# LTC4418_Schematic.net
KiCad netlist of a schematic drawn in EAGLE
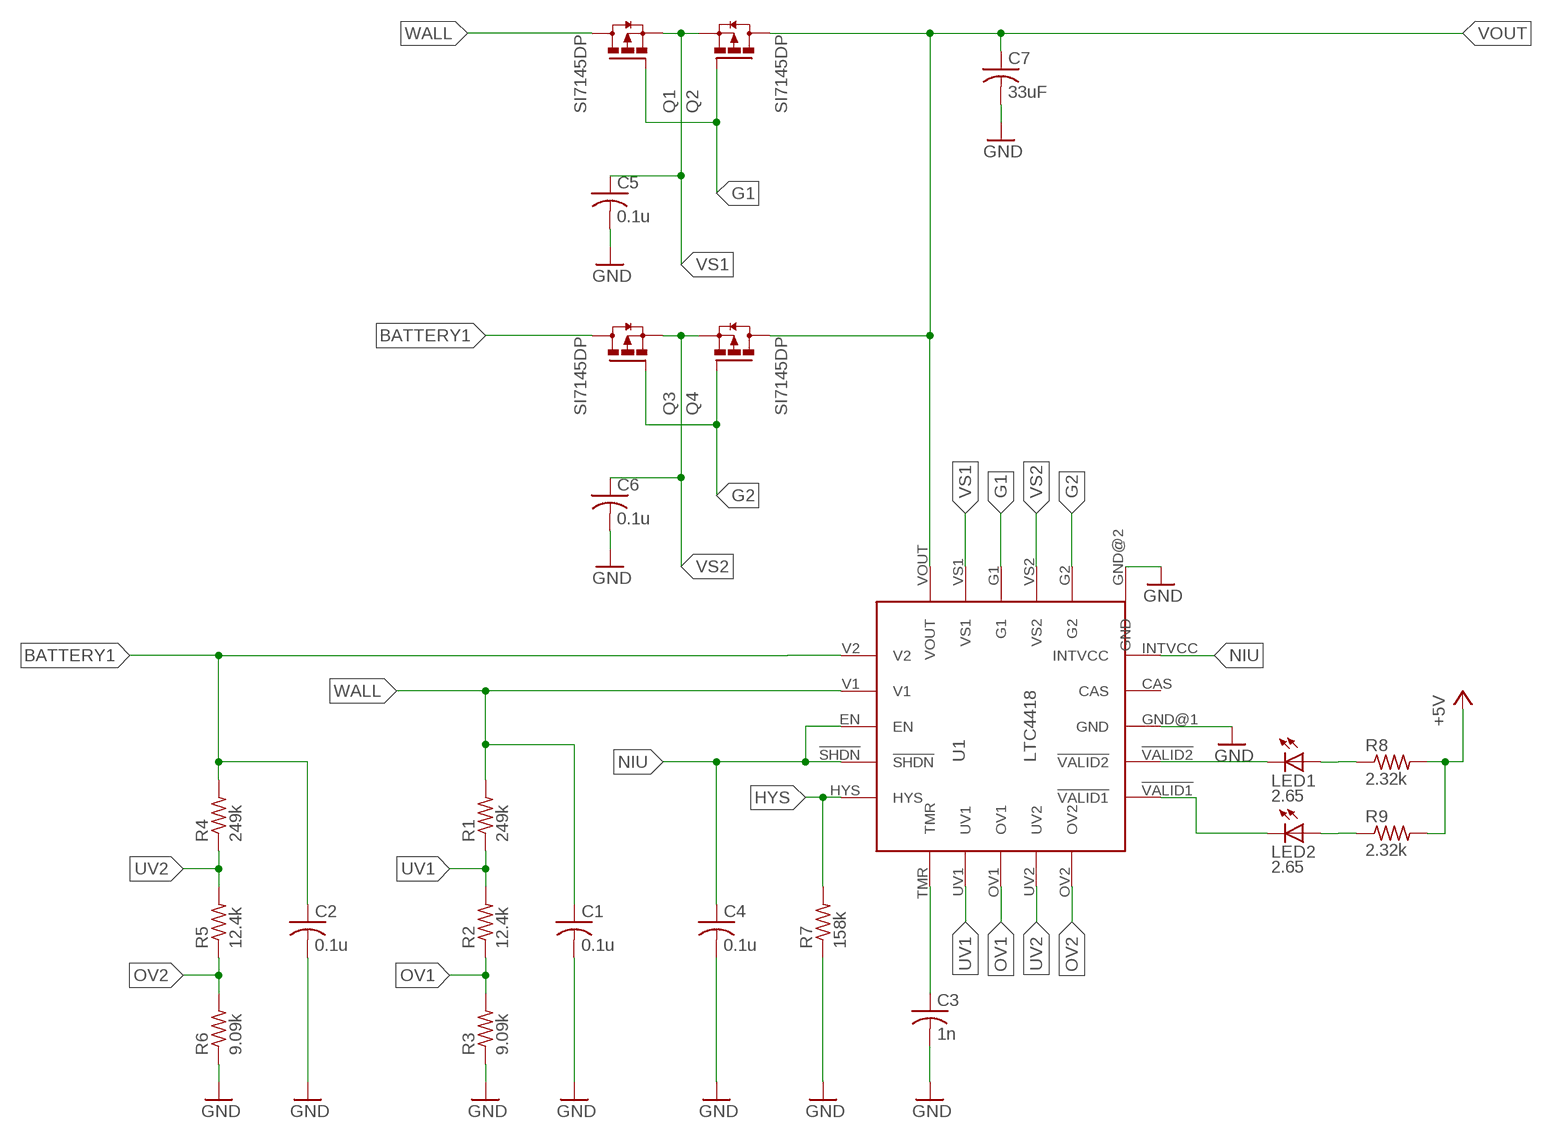
[diagram p0: schematic, sheet 1]

(export (version "E")
  (design (tool "Eeschema 10.0.6"))
  (components
    (comp (ref "C1")
      (value "0.1u")
      (footprint "eagle-import:C1206")
      (libsource (lib "eagle-import") (part "C-USC1206"))
    )
    (comp (ref "C2")
      (value "0.1u")
      (footprint "eagle-import:C1206")
      (libsource (lib "eagle-import") (part "C-USC1206"))
    )
    (comp (ref "C3")
      (value "1n")
      (footprint "eagle-import:C1206")
      (libsource (lib "eagle-import") (part "C-USC1206"))
    )
    (comp (ref "C4")
      (value "0.1u")
      (footprint "eagle-import:C1206")
      (libsource (lib "eagle-import") (part "C-USC1206"))
    )
    (comp (ref "C5")
      (value "0.1u")
      (footprint "eagle-import:C1206")
      (libsource (lib "eagle-import") (part "C-USC1206"))
    )
    (comp (ref "C6")
      (value "0.1u")
      (footprint "eagle-import:C1206")
      (libsource (lib "eagle-import") (part "C-USC1206"))
    )
    (comp (ref "C7")
      (value "33uF")
      (footprint "eagle-import:C1206")
      (libsource (lib "eagle-import") (part "C-USC1206"))
    )
    (comp (ref "LED1")
      (value "2.65")
      (footprint "eagle-import:SML0805")
      (libsource (lib "eagle-import") (part "LEDSML0805"))
    )
    (comp (ref "LED2")
      (value "2.65")
      (footprint "eagle-import:SML0805")
      (libsource (lib "eagle-import") (part "LEDSML0805"))
    )
    (comp (ref "Q1")
      (value "SI7145DP")
      (footprint "eagle-import:SO-8_PPAK_TEST")
      (libsource (lib "eagle-import") (part "SI7145DP"))
    )
    (comp (ref "Q2")
      (value "SI7145DP")
      (footprint "eagle-import:SO-8_PPAK_TEST")
      (libsource (lib "eagle-import") (part "SI7145DP"))
    )
    (comp (ref "Q3")
      (value "SI7145DP")
      (footprint "eagle-import:SO-8_PPAK_TEST")
      (libsource (lib "eagle-import") (part "SI7145DP"))
    )
    (comp (ref "Q4")
      (value "SI7145DP")
      (footprint "eagle-import:SO-8_PPAK_TEST")
      (libsource (lib "eagle-import") (part "SI7145DP"))
    )
    (comp (ref "R1")
      (value "249k")
      (footprint "eagle-import:R1206")
      (libsource (lib "eagle-import") (part "R-US_R1206"))
    )
    (comp (ref "R2")
      (value "12.4k")
      (footprint "eagle-import:R1206")
      (libsource (lib "eagle-import") (part "R-US_R1206"))
    )
    (comp (ref "R3")
      (value "9.09k")
      (footprint "eagle-import:R1206")
      (libsource (lib "eagle-import") (part "R-US_R1206"))
    )
    (comp (ref "R4")
      (value "249k")
      (footprint "eagle-import:R1206")
      (libsource (lib "eagle-import") (part "R-US_R1206"))
    )
    (comp (ref "R5")
      (value "12.4k")
      (footprint "eagle-import:R1206")
      (libsource (lib "eagle-import") (part "R-US_R1206"))
    )
    (comp (ref "R6")
      (value "9.09k")
      (footprint "eagle-import:R1206")
      (libsource (lib "eagle-import") (part "R-US_R1206"))
    )
    (comp (ref "R7")
      (value "158k")
      (footprint "eagle-import:R1206")
      (libsource (lib "eagle-import") (part "R-US_R1206"))
    )
    (comp (ref "R8")
      (value "2.32k")
      (footprint "eagle-import:R1206")
      (libsource (lib "eagle-import") (part "R-US_R1206"))
    )
    (comp (ref "R9")
      (value "2.32k")
      (footprint "eagle-import:R1206")
      (libsource (lib "eagle-import") (part "R-US_R1206"))
    )
    (comp (ref "U1")
      (value "LTC4418")
      (footprint "eagle-import:20-QFN(4X4)")
      (libsource (lib "eagle-import") (part "LTC4418"))
    )
  )
  (nets
    (net (code "1") (name "+5V") (class "Default")
      (node (ref "R8") (pin "2") (pinfunction "2_2") (pintype "passive"))
      (node (ref "R9") (pin "2") (pinfunction "2_2") (pintype "passive"))
    )
    (net (code "2") (name "BATTERY1") (class "Default")
      (node (ref "C2") (pin "1") (pinfunction "1_1") (pintype "passive"))
      (node (ref "Q3") (pin "D@1") (pinfunction "D_D@1") (pintype "passive"))
      (node (ref "Q3") (pin "D@2") (pinfunction "D_D@2") (pintype "passive"))
      (node (ref "Q3") (pin "D@3") (pinfunction "D_D@3") (pintype "passive"))
      (node (ref "Q3") (pin "D@4") (pinfunction "D_D@4") (pintype "passive"))
      (node (ref "Q3") (pin "D@5") (pinfunction "D_D@5") (pintype "passive"))
      (node (ref "R4") (pin "2") (pinfunction "2_2") (pintype "passive"))
      (node (ref "U1") (pin "V2") (pinfunction "V2_V2") (pintype "bidirectional"))
    )
    (net (code "3") (name "G1") (class "Default")
      (node (ref "Q1") (pin "G") (pinfunction "G_G") (pintype "passive"))
      (node (ref "Q2") (pin "G") (pinfunction "G_G") (pintype "passive"))
      (node (ref "U1") (pin "G1") (pinfunction "G1_G1") (pintype "bidirectional"))
    )
    (net (code "4") (name "G2") (class "Default")
      (node (ref "Q3") (pin "G") (pinfunction "G_G") (pintype "passive"))
      (node (ref "Q4") (pin "G") (pinfunction "G_G") (pintype "passive"))
      (node (ref "U1") (pin "G2") (pinfunction "G2_G2") (pintype "bidirectional"))
    )
    (net (code "5") (name "GND") (class "Default")
      (node (ref "C1") (pin "2") (pinfunction "2_2") (pintype "passive"))
      (node (ref "C2") (pin "2") (pinfunction "2_2") (pintype "passive"))
      (node (ref "C3") (pin "2") (pinfunction "2_2") (pintype "passive"))
      (node (ref "C4") (pin "2") (pinfunction "2_2") (pintype "passive"))
      (node (ref "C5") (pin "2") (pinfunction "2_2") (pintype "passive"))
      (node (ref "C6") (pin "2") (pinfunction "2_2") (pintype "passive"))
      (node (ref "C7") (pin "2") (pinfunction "2_2") (pintype "passive"))
      (node (ref "R3") (pin "1") (pinfunction "1_1") (pintype "passive"))
      (node (ref "R6") (pin "1") (pinfunction "1_1") (pintype "passive"))
      (node (ref "R7") (pin "1") (pinfunction "1_1") (pintype "passive"))
      (node (ref "U1") (pin "GND@1") (pinfunction "GND_GND@1") (pintype "power_in"))
      (node (ref "U1") (pin "GND@2") (pinfunction "GND_GND@2") (pintype "power_in"))
    )
    (net (code "6") (name "HYS") (class "Default")
      (node (ref "R7") (pin "2") (pinfunction "2_2") (pintype "passive"))
      (node (ref "U1") (pin "HYS") (pinfunction "HYS_HYS") (pintype "bidirectional"))
    )
    (net (code "7") (name "NIU") (class "Default")
      (node (ref "C4") (pin "1") (pinfunction "1_1") (pintype "passive"))
      (node (ref "U1") (pin "!SHDN") (pinfunction "~{SHDN}_!SHDN") (pintype "bidirectional"))
      (node (ref "U1") (pin "EN") (pinfunction "EN_EN") (pintype "bidirectional"))
      (node (ref "U1") (pin "INTVCC") (pinfunction "INTVCC_INTVCC") (pintype "bidirectional"))
    )
    (net (code "8") (name "Net-(C3-Pad1)") (class "Default")
      (node (ref "C3") (pin "1") (pinfunction "1_1") (pintype "passive"))
      (node (ref "U1") (pin "TMR") (pinfunction "TMR_TMR") (pintype "bidirectional"))
    )
    (net (code "9") (name "Net-(LED1-PadA)") (class "Default")
      (node (ref "LED1") (pin "A") (pinfunction "A_A") (pintype "passive"))
      (node (ref "R8") (pin "1") (pinfunction "1_1") (pintype "passive"))
    )
    (net (code "10") (name "Net-(LED2-PadA)") (class "Default")
      (node (ref "LED2") (pin "A") (pinfunction "A_A") (pintype "passive"))
      (node (ref "R9") (pin "1") (pinfunction "1_1") (pintype "passive"))
    )
    (net (code "11") (name "Net-(U1-~{VALID1})") (class "Default")
      (node (ref "LED2") (pin "C") (pinfunction "C_C") (pintype "passive"))
      (node (ref "U1") (pin "!VALID1") (pinfunction "~{VALID1}_!VALID1") (pintype "bidirectional"))
    )
    (net (code "12") (name "Net-(U1-~{VALID2})") (class "Default")
      (node (ref "LED1") (pin "C") (pinfunction "C_C") (pintype "passive"))
      (node (ref "U1") (pin "!VALID2") (pinfunction "~{VALID2}_!VALID2") (pintype "bidirectional"))
    )
    (net (code "13") (name "OV1") (class "Default")
      (node (ref "R2") (pin "1") (pinfunction "1_1") (pintype "passive"))
      (node (ref "R3") (pin "2") (pinfunction "2_2") (pintype "passive"))
      (node (ref "U1") (pin "OV1") (pinfunction "OV1_OV1") (pintype "bidirectional"))
    )
    (net (code "14") (name "OV2") (class "Default")
      (node (ref "R5") (pin "1") (pinfunction "1_1") (pintype "passive"))
      (node (ref "R6") (pin "2") (pinfunction "2_2") (pintype "passive"))
      (node (ref "U1") (pin "OV2") (pinfunction "OV2_OV2") (pintype "bidirectional"))
    )
    (net (code "15") (name "UV1") (class "Default")
      (node (ref "R1") (pin "1") (pinfunction "1_1") (pintype "passive"))
      (node (ref "R2") (pin "2") (pinfunction "2_2") (pintype "passive"))
      (node (ref "U1") (pin "UV1") (pinfunction "UV1_UV1") (pintype "bidirectional"))
    )
    (net (code "16") (name "UV2") (class "Default")
      (node (ref "R4") (pin "1") (pinfunction "1_1") (pintype "passive"))
      (node (ref "R5") (pin "2") (pinfunction "2_2") (pintype "passive"))
      (node (ref "U1") (pin "UV2") (pinfunction "UV2_UV2") (pintype "bidirectional"))
    )
    (net (code "17") (name "VOUT") (class "Default")
      (node (ref "C7") (pin "1") (pinfunction "1_1") (pintype "passive"))
      (node (ref "Q2") (pin "D@1") (pinfunction "D_D@1") (pintype "passive"))
      (node (ref "Q2") (pin "D@2") (pinfunction "D_D@2") (pintype "passive"))
      (node (ref "Q2") (pin "D@3") (pinfunction "D_D@3") (pintype "passive"))
      (node (ref "Q2") (pin "D@4") (pinfunction "D_D@4") (pintype "passive"))
      (node (ref "Q2") (pin "D@5") (pinfunction "D_D@5") (pintype "passive"))
      (node (ref "Q4") (pin "D@1") (pinfunction "D_D@1") (pintype "passive"))
      (node (ref "Q4") (pin "D@2") (pinfunction "D_D@2") (pintype "passive"))
      (node (ref "Q4") (pin "D@3") (pinfunction "D_D@3") (pintype "passive"))
      (node (ref "Q4") (pin "D@4") (pinfunction "D_D@4") (pintype "passive"))
      (node (ref "Q4") (pin "D@5") (pinfunction "D_D@5") (pintype "passive"))
      (node (ref "U1") (pin "VOUT") (pinfunction "VOUT_VOUT") (pintype "power_in"))
    )
    (net (code "18") (name "VS1") (class "Default")
      (node (ref "C5") (pin "1") (pinfunction "1_1") (pintype "passive"))
      (node (ref "Q1") (pin "S@1") (pinfunction "S_S@1") (pintype "passive"))
      (node (ref "Q1") (pin "S@2") (pinfunction "S_S@2") (pintype "passive"))
      (node (ref "Q1") (pin "S@3") (pinfunction "S_S@3") (pintype "passive"))
      (node (ref "Q2") (pin "S@1") (pinfunction "S_S@1") (pintype "passive"))
      (node (ref "Q2") (pin "S@2") (pinfunction "S_S@2") (pintype "passive"))
      (node (ref "Q2") (pin "S@3") (pinfunction "S_S@3") (pintype "passive"))
      (node (ref "U1") (pin "VS1") (pinfunction "VS1_VS1") (pintype "bidirectional"))
    )
    (net (code "19") (name "VS2") (class "Default")
      (node (ref "C6") (pin "1") (pinfunction "1_1") (pintype "passive"))
      (node (ref "Q3") (pin "S@1") (pinfunction "S_S@1") (pintype "passive"))
      (node (ref "Q3") (pin "S@2") (pinfunction "S_S@2") (pintype "passive"))
      (node (ref "Q3") (pin "S@3") (pinfunction "S_S@3") (pintype "passive"))
      (node (ref "Q4") (pin "S@1") (pinfunction "S_S@1") (pintype "passive"))
      (node (ref "Q4") (pin "S@2") (pinfunction "S_S@2") (pintype "passive"))
      (node (ref "Q4") (pin "S@3") (pinfunction "S_S@3") (pintype "passive"))
      (node (ref "U1") (pin "VS2") (pinfunction "VS2_VS2") (pintype "bidirectional"))
    )
    (net (code "20") (name "WALL") (class "Default")
      (node (ref "C1") (pin "1") (pinfunction "1_1") (pintype "passive"))
      (node (ref "Q1") (pin "D@1") (pinfunction "D_D@1") (pintype "passive"))
      (node (ref "Q1") (pin "D@2") (pinfunction "D_D@2") (pintype "passive"))
      (node (ref "Q1") (pin "D@3") (pinfunction "D_D@3") (pintype "passive"))
      (node (ref "Q1") (pin "D@4") (pinfunction "D_D@4") (pintype "passive"))
      (node (ref "Q1") (pin "D@5") (pinfunction "D_D@5") (pintype "passive"))
      (node (ref "R1") (pin "2") (pinfunction "2_2") (pintype "passive"))
      (node (ref "U1") (pin "V1") (pinfunction "V1_V1") (pintype "bidirectional"))
    )
    (net (code "21") (name "unconnected-(U1-PadCAS)") (class "Default")
      (node (ref "U1") (pin "CAS") (pinfunction "CAS_CAS") (pintype "bidirectional"))
    )
  )
)
